# Sheet1.net
KiCad netlist of a schematic drawn in Altium Designer
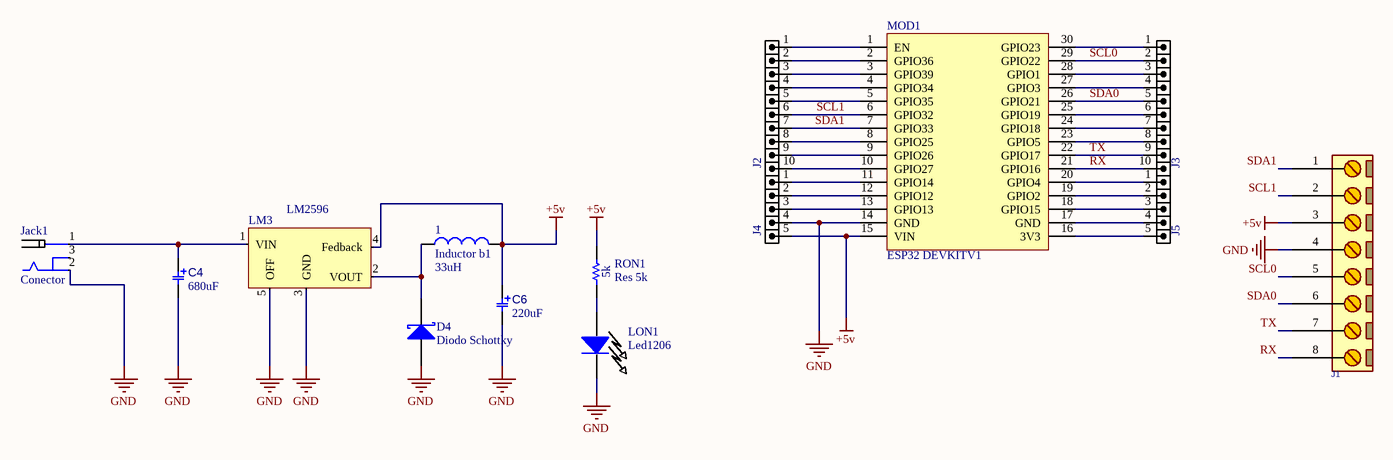
[diagram p0: Sheet1.SchDoc]

(export (version "E")
  (design (tool "Eeschema 10.0.6"))
  (components
    (comp (ref "1")
      (value "Inductor b1")
      (footprint "CYH74-33UH")
      (description "Inductor")
      (fields (field (name "ALTIUM_VALUE") "33uH") (field (name "PUBLISHER") "Altium Limited"))
      (libsource (lib "Miscellaneous Devices") (part "Inductor"))
    )
    (comp (ref "C4")
      (value "~")
      (footprint "CAP_EEEFK1E681SP")
      (description "Capacitor;  Alum Electrolytic;  Cap 330 uF;  Tol 20%;  Vol-Rtg 25 VDC;  SMT;  8x10.5;  CT")
      (fields
        (field (name "MANUFACTURER") "Panasonic")
        (field (name "MANUFACTURER PART NUMBER") "EEE-1EA331UP")
        (field (name "CAPACITANCE") "680uF")
      )
      (libsource (lib "Capacitores_SMD") (part "CAP_SMD_EL_330u25V"))
    )
    (comp (ref "C6")
      (value "~")
      (footprint "RVT220UF16V67RV0015")
      (description "Capacitor;  Alum Electrolytic;  Cap 330 uF;  Tol 20%;  Vol-Rtg 25 VDC;  SMT;  8x10.5;  CT")
      (fields
        (field (name "MANUFACTURER") "Panasonic")
        (field (name "MANUFACTURER PART NUMBER") "EEE-1EA331UP")
        (field (name "CAPACITANCE") "220uF")
      )
      (libsource (lib "Capacitores_SMD") (part "CAP_SMD_EL_330u25V"))
    )
    (comp (ref "D4")
      (value "Diodo Schottky")
      (footprint "DO-214AC-2")
      (libsource (lib "MisLibreriasJavier") (part "Diodo Schottky"))
    )
    (comp (ref "J1")
      (value "CONN_TB8")
      (footprint "TBG_8")
      (description "CONN, TERMINAL BLOCK, 5.08mm pitch")
      (libsource (lib "linrerias_general_nino") (part "Bloque Terminal 8"))
    )
    (comp (ref "J2")
      (value "HDR1X10")
      (footprint "HDR_M_1X10")
      (description "CONN, HEADER, Male, pitch: 2.54mm, 10POS")
      (fields (field (name "MANUFACTURER") "?"))
      (libsource (lib "linrerias_general_nino") (part "Header Male THT 1x10"))
    )
    (comp (ref "J3")
      (value "HDR1X10")
      (footprint "HDR_M_1X10")
      (description "CONN, HEADER, Male, pitch: 2.54mm, 10POS")
      (fields (field (name "MANUFACTURER") "?"))
      (libsource (lib "") (part "Header Male THT 1x10_1"))
    )
    (comp (ref "J4")
      (value "HDR1X5")
      (footprint "HDR_M_1X5")
      (description "CONN, HEADER, Male, pitch: 2.54mm, 5POS")
      (fields (field (name "MANUFACTURER") "?"))
      (libsource (lib "") (part "Header Male THT 1x5_1"))
    )
    (comp (ref "J5")
      (value "HDR1X5")
      (footprint "HDR_M_1X5")
      (description "CONN, HEADER, Male, pitch: 2.54mm, 5POS")
      (fields (field (name "MANUFACTURER") "?"))
      (libsource (lib "linrerias_general_nino") (part "Header Male THT 1x5"))
    )
    (comp (ref "Jack1")
      (value "Conector")
      (footprint "Conector JACK")
      (libsource (lib "ENTRENADOR_18F") (part "Conector"))
    )
    (comp (ref "LM3")
      (value "LM2596")
      (footprint "LM2596")
      (libsource (lib "MisLibreriasJavier") (part "LM2596"))
    )
    (comp (ref "LON1")
      (value "Led1206")
      (footprint "LED1206")
      (description "NCD1206R1")
      (libsource (lib "MisLibreriasJavier") (part "Led1206"))
    )
    (comp (ref "MOD1")
      (value "ESP32 DEVKITV1")
      (footprint "HDR_F_1X15")
      (libsource (lib "Integrated_Library1_denilson") (part "ESP32 DEVKITV1"))
    )
    (comp (ref "RON1")
      (value "Res 5k")
      (footprint "RES 0805 - 5k")
      (description "ARG05DTC5001")
      (libsource (lib "MisLibreriasJavier") (part "Res 5k"))
    )
  )
  (nets
    (net (code "1") (name "+5v") (class "Default")
      (node (ref "1") (pin "2") (pinfunction "2_2") (pintype "passive"))
      (node (ref "C6") (pin "1") (pinfunction "1_1") (pintype "passive"))
      (node (ref "J1") (pin "3") (pinfunction "3_3") (pintype "passive"))
      (node (ref "J4") (pin "5") (pinfunction "5_5") (pintype "passive"))
      (node (ref "LM3") (pin "4") (pinfunction "Fedback_4") (pintype "passive"))
      (node (ref "MOD1") (pin "15") (pinfunction "VIN_15") (pintype "passive"))
      (node (ref "RON1") (pin "2") (pinfunction "2_2") (pintype "passive"))
    )
    (net (code "2") (name "/RX") (class "Default")
      (node (ref "J1") (pin "8") (pinfunction "8_8") (pintype "passive"))
      (node (ref "J3") (pin "10") (pinfunction "10_10") (pintype "passive"))
      (node (ref "MOD1") (pin "21") (pinfunction "GPIO16_21") (pintype "passive"))
    )
    (net (code "3") (name "/SCL0") (class "Default")
      (node (ref "J1") (pin "5") (pinfunction "5_5") (pintype "passive"))
      (node (ref "J3") (pin "2") (pinfunction "2_2") (pintype "passive"))
      (node (ref "MOD1") (pin "29") (pinfunction "GPIO22_29") (pintype "passive"))
    )
    (net (code "4") (name "/SCL1") (class "Default")
      (node (ref "J1") (pin "2") (pinfunction "2_2") (pintype "passive"))
      (node (ref "J2") (pin "6") (pinfunction "6_6") (pintype "passive"))
      (node (ref "MOD1") (pin "6") (pinfunction "GPIO32_6") (pintype "passive"))
    )
    (net (code "5") (name "/SDA0") (class "Default")
      (node (ref "J1") (pin "6") (pinfunction "6_6") (pintype "passive"))
      (node (ref "J3") (pin "5") (pinfunction "5_5") (pintype "passive"))
      (node (ref "MOD1") (pin "26") (pinfunction "GPIO21_26") (pintype "passive"))
    )
    (net (code "6") (name "/SDA1") (class "Default")
      (node (ref "J1") (pin "1") (pinfunction "1_1") (pintype "passive"))
      (node (ref "J2") (pin "7") (pinfunction "7_7") (pintype "passive"))
      (node (ref "MOD1") (pin "7") (pinfunction "GPIO33_7") (pintype "passive"))
    )
    (net (code "7") (name "/TX") (class "Default")
      (node (ref "J1") (pin "7") (pinfunction "7_7") (pintype "passive"))
      (node (ref "J3") (pin "9") (pinfunction "9_9") (pintype "passive"))
      (node (ref "MOD1") (pin "22") (pinfunction "GPIO17_22") (pintype "passive"))
    )
    (net (code "8") (name "GND") (class "Default")
      (node (ref "C4") (pin "2") (pinfunction "2_2") (pintype "passive"))
      (node (ref "C6") (pin "2") (pinfunction "2_2") (pintype "passive"))
      (node (ref "D4") (pin "2") (pinfunction "A_2") (pintype "passive"))
      (node (ref "J1") (pin "4") (pinfunction "4_4") (pintype "passive"))
      (node (ref "J4") (pin "4") (pinfunction "4_4") (pintype "passive"))
      (node (ref "Jack1") (pin "2") (pinfunction "GND_2") (pintype "passive"))
      (node (ref "LM3") (pin "3") (pinfunction "GND_3") (pintype "passive"))
      (node (ref "LM3") (pin "5") (pinfunction "OFF_5") (pintype "passive"))
      (node (ref "LON1") (pin "2") (pinfunction "Càtodo_2") (pintype "passive"))
      (node (ref "MOD1") (pin "14") (pinfunction "GND_14") (pintype "passive"))
    )
    (net (code "9") (name "Net-(D4-K)") (class "Default")
      (node (ref "1") (pin "1") (pinfunction "1_1") (pintype "passive"))
      (node (ref "D4") (pin "1") (pinfunction "K_1") (pintype "passive"))
      (node (ref "LM3") (pin "2") (pinfunction "VOUT_2") (pintype "passive"))
    )
    (net (code "10") (name "Net-(J5-Pad4)") (class "Default")
      (node (ref "J5") (pin "4") (pinfunction "4_4") (pintype "passive"))
      (node (ref "MOD1") (pin "17") (pinfunction "GND_17") (pintype "passive"))
    )
    (net (code "11") (name "Net-(Jack1-V+)") (class "Default")
      (node (ref "C4") (pin "1") (pinfunction "1_1") (pintype "passive"))
      (node (ref "Jack1") (pin "1") (pinfunction "V+_1") (pintype "passive"))
      (node (ref "LM3") (pin "1") (pinfunction "VIN_1") (pintype "passive"))
    )
    (net (code "12") (name "Net-(LON1-Ànodo)") (class "Default")
      (node (ref "LON1") (pin "1") (pinfunction "Ànodo_1") (pintype "passive"))
      (node (ref "RON1") (pin "1") (pinfunction "1_1") (pintype "passive"))
    )
    (net (code "13") (name "Net-(MOD1-3V3)") (class "Default")
      (node (ref "J5") (pin "5") (pinfunction "5_5") (pintype "passive"))
      (node (ref "MOD1") (pin "16") (pinfunction "3V3_16") (pintype "passive"))
    )
    (net (code "14") (name "Net-(MOD1-EN)") (class "Default")
      (node (ref "J2") (pin "1") (pinfunction "1_1") (pintype "passive"))
      (node (ref "MOD1") (pin "1") (pinfunction "EN_1") (pintype "passive"))
    )
    (net (code "15") (name "Net-(MOD1-GPIO1)") (class "Default")
      (node (ref "J3") (pin "3") (pinfunction "3_3") (pintype "passive"))
      (node (ref "MOD1") (pin "28") (pinfunction "GPIO1_28") (pintype "passive"))
    )
    (net (code "16") (name "Net-(MOD1-GPIO2)") (class "Default")
      (node (ref "J5") (pin "2") (pinfunction "2_2") (pintype "passive"))
      (node (ref "MOD1") (pin "19") (pinfunction "GPIO2_19") (pintype "passive"))
    )
    (net (code "17") (name "Net-(MOD1-GPIO3)") (class "Default")
      (node (ref "J3") (pin "4") (pinfunction "4_4") (pintype "passive"))
      (node (ref "MOD1") (pin "27") (pinfunction "GPIO3_27") (pintype "passive"))
    )
    (net (code "18") (name "Net-(MOD1-GPIO4)") (class "Default")
      (node (ref "J5") (pin "1") (pinfunction "1_1") (pintype "passive"))
      (node (ref "MOD1") (pin "20") (pinfunction "GPIO4_20") (pintype "passive"))
    )
    (net (code "19") (name "Net-(MOD1-GPIO5)") (class "Default")
      (node (ref "J3") (pin "8") (pinfunction "8_8") (pintype "passive"))
      (node (ref "MOD1") (pin "23") (pinfunction "GPIO5_23") (pintype "passive"))
    )
    (net (code "20") (name "Net-(MOD1-GPIO12)") (class "Default")
      (node (ref "J4") (pin "2") (pinfunction "2_2") (pintype "passive"))
      (node (ref "MOD1") (pin "12") (pinfunction "GPIO12_12") (pintype "passive"))
    )
    (net (code "21") (name "Net-(MOD1-GPIO13)") (class "Default")
      (node (ref "J4") (pin "3") (pinfunction "3_3") (pintype "passive"))
      (node (ref "MOD1") (pin "13") (pinfunction "GPIO13_13") (pintype "passive"))
    )
    (net (code "22") (name "Net-(MOD1-GPIO14)") (class "Default")
      (node (ref "J4") (pin "1") (pinfunction "1_1") (pintype "passive"))
      (node (ref "MOD1") (pin "11") (pinfunction "GPIO14_11") (pintype "passive"))
    )
    (net (code "23") (name "Net-(MOD1-GPIO15)") (class "Default")
      (node (ref "J5") (pin "3") (pinfunction "3_3") (pintype "passive"))
      (node (ref "MOD1") (pin "18") (pinfunction "GPIO15_18") (pintype "passive"))
    )
    (net (code "24") (name "Net-(MOD1-GPIO18)") (class "Default")
      (node (ref "J3") (pin "7") (pinfunction "7_7") (pintype "passive"))
      (node (ref "MOD1") (pin "24") (pinfunction "GPIO18_24") (pintype "passive"))
    )
    (net (code "25") (name "Net-(MOD1-GPIO19)") (class "Default")
      (node (ref "J3") (pin "6") (pinfunction "6_6") (pintype "passive"))
      (node (ref "MOD1") (pin "25") (pinfunction "GPIO19_25") (pintype "passive"))
    )
    (net (code "26") (name "Net-(MOD1-GPIO23)") (class "Default")
      (node (ref "J3") (pin "1") (pinfunction "1_1") (pintype "passive"))
      (node (ref "MOD1") (pin "30") (pinfunction "GPIO23_30") (pintype "passive"))
    )
    (net (code "27") (name "Net-(MOD1-GPIO25)") (class "Default")
      (node (ref "J2") (pin "8") (pinfunction "8_8") (pintype "passive"))
      (node (ref "MOD1") (pin "8") (pinfunction "GPIO25_8") (pintype "passive"))
    )
    (net (code "28") (name "Net-(MOD1-GPIO26)") (class "Default")
      (node (ref "J2") (pin "9") (pinfunction "9_9") (pintype "passive"))
      (node (ref "MOD1") (pin "9") (pinfunction "GPIO26_9") (pintype "passive"))
    )
    (net (code "29") (name "Net-(MOD1-GPIO27)") (class "Default")
      (node (ref "J2") (pin "10") (pinfunction "10_10") (pintype "passive"))
      (node (ref "MOD1") (pin "10") (pinfunction "GPIO27_10") (pintype "passive"))
    )
    (net (code "30") (name "Net-(MOD1-GPIO34)") (class "Default")
      (node (ref "J2") (pin "4") (pinfunction "4_4") (pintype "passive"))
      (node (ref "MOD1") (pin "4") (pinfunction "GPIO34_4") (pintype "passive"))
    )
    (net (code "31") (name "Net-(MOD1-GPIO35)") (class "Default")
      (node (ref "J2") (pin "5") (pinfunction "5_5") (pintype "passive"))
      (node (ref "MOD1") (pin "5") (pinfunction "GPIO35_5") (pintype "passive"))
    )
    (net (code "32") (name "Net-(MOD1-GPIO36)") (class "Default")
      (node (ref "J2") (pin "2") (pinfunction "2_2") (pintype "passive"))
      (node (ref "MOD1") (pin "2") (pinfunction "GPIO36_2") (pintype "passive"))
    )
    (net (code "33") (name "Net-(MOD1-GPIO39)") (class "Default")
      (node (ref "J2") (pin "3") (pinfunction "3_3") (pintype "passive"))
      (node (ref "MOD1") (pin "3") (pinfunction "GPIO39_3") (pintype "passive"))
    )
    (net (code "34") (name "unconnected-(Jack1-Pad3)") (class "Default")
      (node (ref "Jack1") (pin "3") (pintype "passive"))
    )
  )
)
